# H0BR4.net
KiCad netlist of a schematic drawn in EAGLE
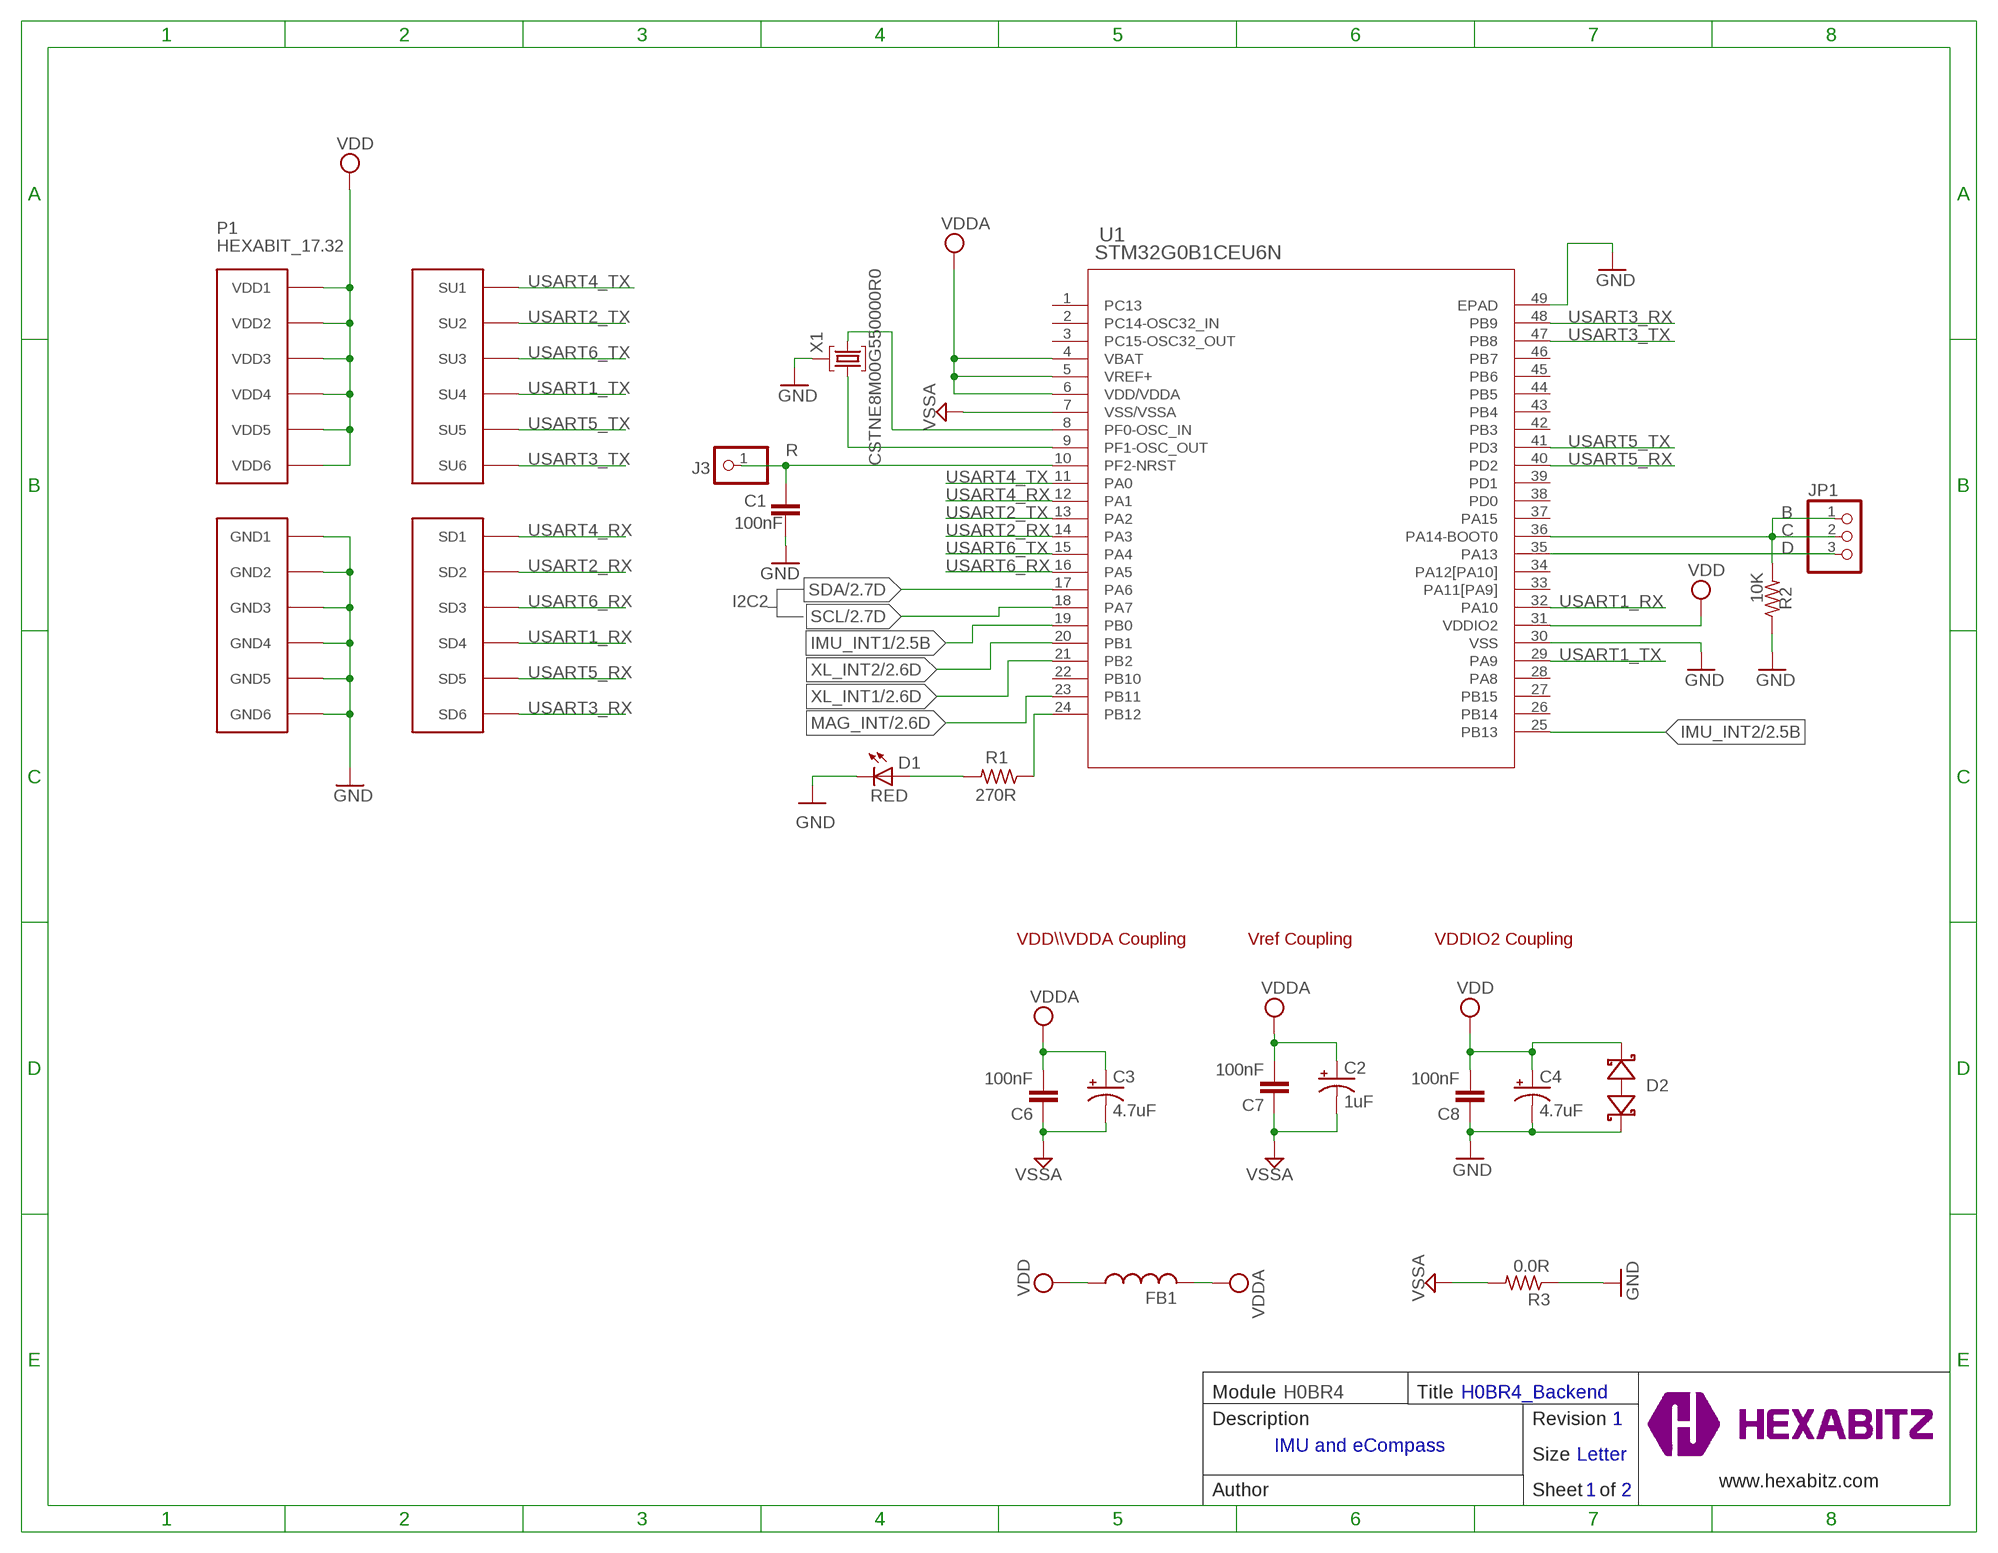
[diagram p0: schematic, sheet 1]
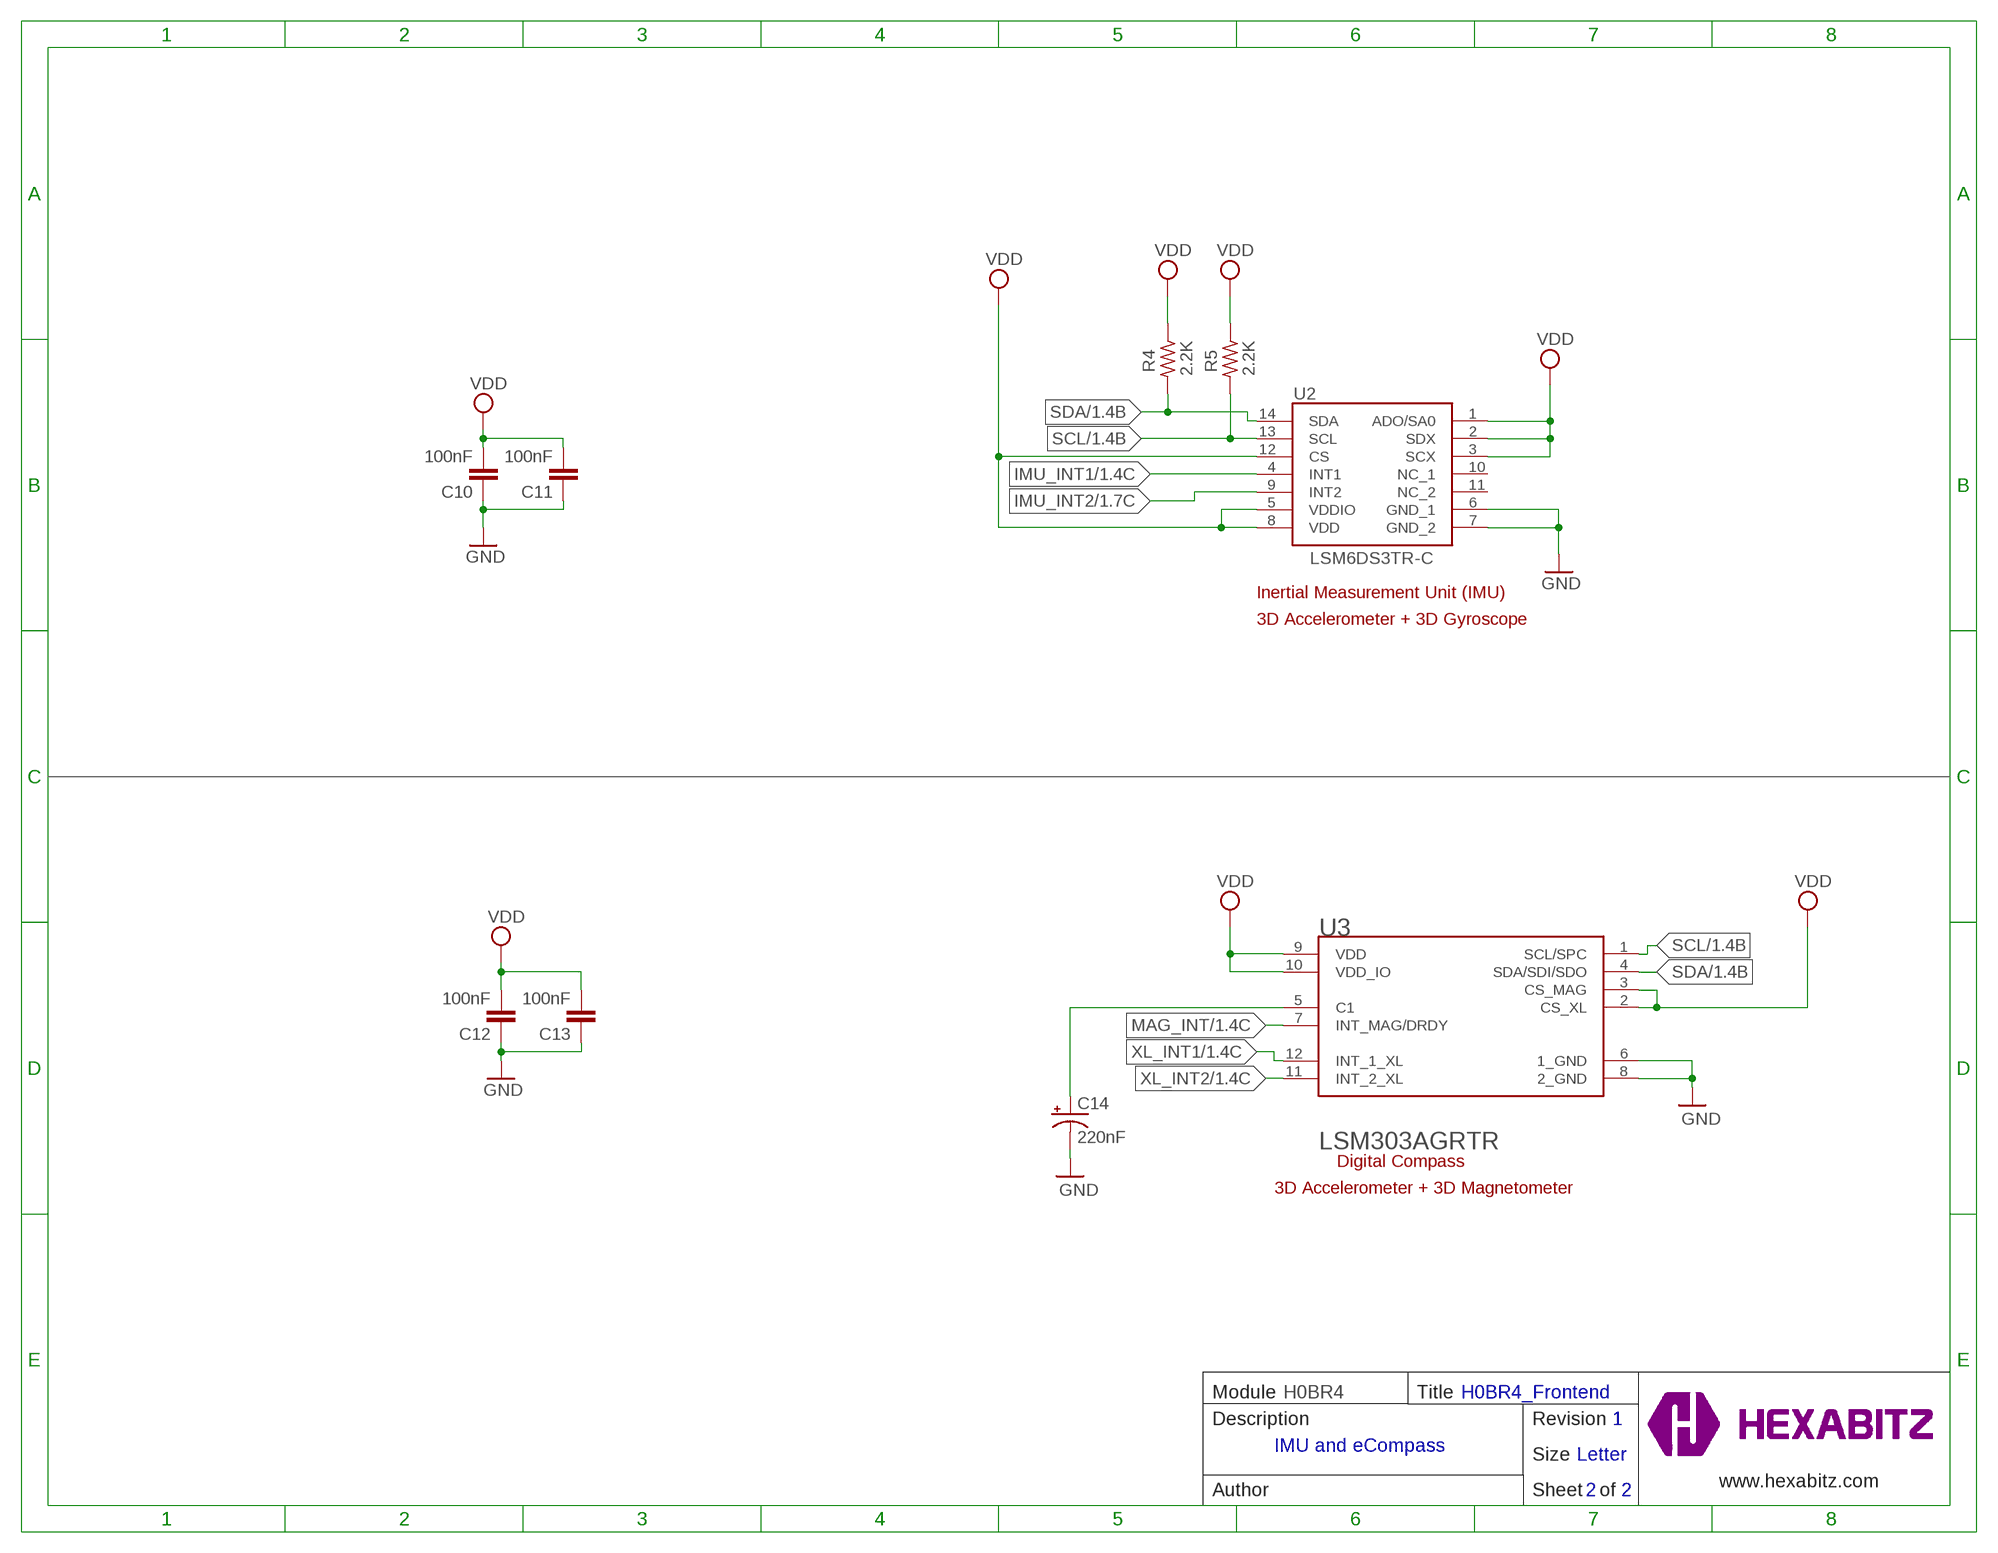
[diagram p1: schematic, sheet 2]

(export (version "E")
  (design (tool "Eeschema 10.0.6"))
  (components
    (comp (ref "C1")
      (value "100nF")
      (footprint "eagle-import:C-0603")
      (fields
        (field (name "CAPACITANCE") "100nF")
        (field (name "MFN") "AVX CORPORATION")
        (field (name "MPN") "'0603YC104K4T2A")
        (field (name "OCTOPART_URL") "'https://octopart.com/0603yc104k4t2a-avx+interconnect+%2F+elco-8120651")
        (field (name "TOLERANCE") "10%")
        (field (name "VOLTAGE_RATING") "16.0 V")
      )
      (libsource (lib "eagle-import") (part "C-0603"))
    )
    (comp (ref "C2")
      (value "1uF")
      (footprint "eagle-import:C-0805-POL")
      (fields
        (field (name "CAPACITANCE") "1.00uF")
        (field (name "MFN") "'YAGEO [VA]")
        (field (name "MPN") "'CC0805KKX7R7BB105")
        (field (name "OCTOPART_URL") "https://octopart.com/cc0805kkx7r7bb105-yageo-8376555?r=sp")
        (field (name "TOLERANCE") "10%")
        (field (name "VOLTAGE_RATING") "16.0 V")
      )
      (libsource (lib "eagle-import") (part "C-0805-POL"))
    )
    (comp (ref "C3")
      (value "4.7uF")
      (footprint "eagle-import:C-0805-POL")
      (fields
        (field (name "CAPACITANCE") "4.7uF")
        (field (name "MFN") "Panasonic")
        (field (name "MPN") "10TPU4R7MSI")
        (field (name "OCTOPART_URL") "https://octopart.com/10tpu4r7msi-panasonic-29487748")
        (field (name "TOLERANCE") "20%")
        (field (name "VOLTAGE_RATING") "10.0 V")
      )
      (libsource (lib "eagle-import") (part "C-0805-POL"))
    )
    (comp (ref "C4")
      (value "4.7uF")
      (footprint "eagle-import:C-0805-POL")
      (fields
        (field (name "CAPACITANCE") "4.7uF")
        (field (name "MFN") "Panasonic")
        (field (name "MPN") "10TPU4R7MSI")
        (field (name "OCTOPART_URL") "https://octopart.com/10tpu4r7msi-panasonic-29487748")
        (field (name "TOLERANCE") "20%")
        (field (name "VOLTAGE_RATING") "10.0 V")
      )
      (libsource (lib "eagle-import") (part "C-0805-POL"))
    )
    (comp (ref "C6")
      (value "100nF")
      (footprint "eagle-import:C-0603")
      (fields
        (field (name "CAPACITANCE") "100nF")
        (field (name "MFN") "AVX CORPORATION")
        (field (name "MPN") "'0603YC104K4T2A")
        (field (name "OCTOPART_URL") "'https://octopart.com/0603yc104k4t2a-avx+interconnect+%2F+elco-8120651")
        (field (name "TOLERANCE") "10%")
        (field (name "VOLTAGE_RATING") "16.0 V")
      )
      (libsource (lib "eagle-import") (part "C-0603"))
    )
    (comp (ref "C7")
      (value "100nF")
      (footprint "eagle-import:C-0603")
      (fields
        (field (name "CAPACITANCE") "100nF")
        (field (name "MFN") "AVX CORPORATION")
        (field (name "MPN") "'0603YC104K4T2A")
        (field (name "OCTOPART_URL") "'https://octopart.com/0603yc104k4t2a-avx+interconnect+%2F+elco-8120651")
        (field (name "TOLERANCE") "10%")
        (field (name "VOLTAGE_RATING") "16.0 V")
      )
      (libsource (lib "eagle-import") (part "C-0603"))
    )
    (comp (ref "C8")
      (value "100nF")
      (footprint "eagle-import:C-0603")
      (fields
        (field (name "CAPACITANCE") "100nF")
        (field (name "MFN") "AVX CORPORATION")
        (field (name "MPN") "'0603YC104K4T2A")
        (field (name "OCTOPART_URL") "'https://octopart.com/0603yc104k4t2a-avx+interconnect+%2F+elco-8120651")
        (field (name "TOLERANCE") "10%")
        (field (name "VOLTAGE_RATING") "16.0 V")
      )
      (libsource (lib "eagle-import") (part "C-0603"))
    )
    (comp (ref "D1")
      (value "RED")
      (footprint "eagle-import:VLMS1300-GS08")
      (fields (field (name "MPN") "VLMS1300-GS08"))
      (libsource (lib "eagle-import") (part "VLMS1300-GS08"))
    )
    (comp (ref "D2")
      (value "BOURNS_CDSOD323-T03SCBOURNS_CDSOD323-T03SC_0_0")
      (footprint "eagle-import:BOURNS_CDSOD323-T03SC_0")
      (fields (field (name "MPN") "CDSOD323-T03SC"))
      (libsource (lib "eagle-import") (part "BOURNS_CDSOD323-T03SCBOURNS_CDSOD323-T03SC_0_0"))
    )
    (comp (ref "FB1")
      (value "FB-TDK_MMZ1608Y300B")
      (footprint "eagle-import:FB-TDK_MMZ1608Y300B")
      (fields
        (field (name "MFN") "TDK ")
        (field (name "MPN") "MMZ1608Y300BTA00")
        (field (name "OCTOPART_URL") "https://octopart.com/mmz1608y300bta00-tdk-7906990?r=sp")
      )
      (libsource (lib "eagle-import") (part "FB-TDK_MMZ1608Y300B"))
    )
    (comp (ref "J3")
      (value "PINHD-1X1")
      (footprint "eagle-import:1X01")
      (fields (field (name "MPN") "87227-1"))
      (libsource (lib "eagle-import") (part "PINHD-1X1"))
    )
    (comp (ref "JP1")
      (value "PINHD-1X3")
      (footprint "eagle-import:1X03")
      (libsource (lib "eagle-import") (part "PINHD-1X3"))
    )
    (comp (ref "P1")
      (value "HEXABIT_17.32")
      (footprint "eagle-import:HEXABIT_17.32")
      (libsource (lib "eagle-import") (part "HEXABIT_?17.32"))
    )
    (comp (ref "R1")
      (value "270R")
      (footprint "eagle-import:R-0603")
      (fields
        (field (name "MFN") "'Panasonic")
        (field (name "MPN") "'ERJ-3GEYJ271V")
        (field (name "OCTOPART_URL") "https://octopart.com/erj-3geyj271v-panasonic-55560546?r=sp")
        (field (name "RESISTANCE") "270R")
      )
      (libsource (lib "eagle-import") (part "R-0603"))
    )
    (comp (ref "R2")
      (value "10K")
      (footprint "eagle-import:R-0603")
      (fields
        (field (name "MFN") "Vishay")
        (field (name "MPN") "'060300J0103T5E")
        (field (name "OCTOPART_URL") "https://octopart.com/search?q=060300J0103T5E&currency=USD&specs=0")
        (field (name "RESISTANCE") "10K")
      )
      (libsource (lib "eagle-import") (part "R-0603"))
    )
    (comp (ref "R3")
      (value "0.0R")
      (footprint "eagle-import:R-0603")
      (fields
        (field (name "MFN") "YAGEO [VR]")
        (field (name "MPN") "RC0603JR-070RL")
        (field (name "OCTOPART_URL") "https://octopart.com/rc0603jr-070rl-yageo-1241539?r=sp")
        (field (name "RESISTANCE") "0R")
      )
      (libsource (lib "eagle-import") (part "R-0603"))
    )
    (comp (ref "TRIMBLE-LOGO1")
      (value "HEXA-LOGO")
      (footprint "eagle-import:HEXA-LOGO")
      (libsource (lib "eagle-import") (part "HEXA-LOGO"))
    )
    (comp (ref "U1")
      (value "STM32G0B1CEU6N")
      (footprint "eagle-import:HEXABITZ_ICS_QFN_B1CEU6_STM-L")
      (libsource (lib "eagle-import") (part "STM32G0B1CEU6N"))
    )
    (comp (ref "X1")
      (value "CSTNE8M00G550000R0")
      (footprint "eagle-import:XTALL_CSTCE8M00G52")
      (fields
        (field (name "MPN") "CSTCE8M00G52Z-R0")
        (field (name "MPN_1") "CSTNE8M00G550000R0")
        (field (name "OCTOPART_URL") "https://octopart.com/cstne8m00g550000r0-murata-91406934?r=sp")
      )
      (libsource (lib "eagle-import") (part "XTALL_CSTCE8M00G52"))
    )
    (comp (ref "C10")
      (value "100nF")
      (footprint "eagle-import:C-0603")
      (fields
        (field (name "CAPACITANCE") "100nF")
        (field (name "MFN") "AVX CORPORATION")
        (field (name "MPN") "'0603YC104K4T2A")
        (field (name "OCTOPART_URL") "'https://octopart.com/0603yc104k4t2a-avx+interconnect+%2F+elco-8120651")
        (field (name "TOLERANCE") "10%")
        (field (name "VOLTAGE_RATING") "16.0 V")
      )
      (libsource (lib "eagle-import") (part "C-0603"))
    )
    (comp (ref "C11")
      (value "100nF")
      (footprint "eagle-import:C-0603")
      (fields
        (field (name "CAPACITANCE") "100nF")
        (field (name "MFN") "AVX CORPORATION")
        (field (name "MPN") "'0603YC104K4T2A")
        (field (name "OCTOPART_URL") "'https://octopart.com/0603yc104k4t2a-avx+interconnect+%2F+elco-8120651")
        (field (name "TOLERANCE") "10%")
        (field (name "VOLTAGE_RATING") "16.0 V")
      )
      (libsource (lib "eagle-import") (part "C-0603"))
    )
    (comp (ref "C12")
      (value "100nF")
      (footprint "eagle-import:C-0603")
      (fields
        (field (name "CAPACITANCE") "100nF")
        (field (name "MFN") "AVX CORPORATION")
        (field (name "MPN") "'0603YC104K4T2A")
        (field (name "OCTOPART_URL") "'https://octopart.com/0603yc104k4t2a-avx+interconnect+%2F+elco-8120651")
        (field (name "TOLERANCE") "10%")
        (field (name "VOLTAGE_RATING") "16.0 V")
      )
      (libsource (lib "eagle-import") (part "C-0603"))
    )
    (comp (ref "C13")
      (value "100nF")
      (footprint "eagle-import:C-0603")
      (fields
        (field (name "CAPACITANCE") "100nF")
        (field (name "MFN") "AVX CORPORATION")
        (field (name "MPN") "'0603YC104K4T2A")
        (field (name "OCTOPART_URL") "'https://octopart.com/0603yc104k4t2a-avx+interconnect+%2F+elco-8120651")
        (field (name "TOLERANCE") "10%")
        (field (name "VOLTAGE_RATING") "16.0 V")
      )
      (libsource (lib "eagle-import") (part "C-0603"))
    )
    (comp (ref "C14")
      (value "220nF")
      (footprint "eagle-import:C-0805-POL")
      (fields
        (field (name "CAPACITANCE") "4.7uF")
        (field (name "MFN") "KEMET ")
        (field (name "MPN") "C0805C224K1RACTU")
        (field (name "OCTOPART_URL") "https://octopart.com/c0805c224k1ractu-kemet-12818106?r=sp")
        (field (name "TOLERANCE") "20%")
        (field (name "VOLTAGE_RATING") "10.0 V")
      )
      (libsource (lib "eagle-import") (part "C-0805-POL"))
    )
    (comp (ref "R4")
      (value "2.2K")
      (footprint "eagle-import:R-0603")
      (fields
        (field (name "MFN") "Yageo")
        (field (name "MPN") "RC0603FR-072K2L")
        (field (name "OCTOPART_URL") "https://octopart.com/rc0603fr-072k2l-yageo-1214512?r=sp")
        (field (name "RESISTANCE") "2.2K Ohm")
        (field (name "TOLERANCE") "5%")
      )
      (libsource (lib "eagle-import") (part "R-0603"))
    )
    (comp (ref "R5")
      (value "2.2K")
      (footprint "eagle-import:R-0603")
      (fields
        (field (name "MFN") "Yageo")
        (field (name "MPN") "RC0603FR-072K2L")
        (field (name "OCTOPART_URL") "https://octopart.com/rc0603fr-072k2l-yageo-1214512?r=sp")
        (field (name "RESISTANCE") "2.2K Ohm")
        (field (name "TOLERANCE") "5%")
      )
      (libsource (lib "eagle-import") (part "R-0603"))
    )
    (comp (ref "U2")
      (value "LSM6DS3TR-C")
      (footprint "eagle-import:LGA-14(2.5X3X0.86)")
      (libsource (lib "eagle-import") (part "LSM6DS3TR-C"))
    )
    (comp (ref "U3")
      (value "STMICROELECTRONICS_LSM303AGRTRSTMICROELECTRONICS_LSM303AGRTR_0_0")
      (footprint "eagle-import:STMICROELECTRONICS_LSM303AGRTR_0")
      (fields
        (field (name "DIGIKEY_PART_NUMBER") "497-16527-1-ND")
        (field (name "MOUSER_PART_NUMBER") "511-LSM303AGRTR")
        (field (name "MPN") "LSM303AGRTR")
      )
      (libsource (lib "eagle-import") (part "STMICROELECTRONICS_LSM303AGRTRSTMICROELECTRONICS_LSM303AGRTR_0_0"))
    )
  )
  (nets
    (net (code "1") (name "C") (class "Default")
      (node (ref "JP1") (pin "1") (pinfunction "1_1") (pintype "passive"))
      (node (ref "JP1") (pin "2") (pinfunction "2_2") (pintype "passive"))
      (node (ref "R2") (pin "2") (pinfunction "2_2") (pintype "passive"))
      (node (ref "U1") (pin "36") (pinfunction "PA14-BOOT0_36") (pintype "bidirectional"))
    )
    (net (code "2") (name "D") (class "Default")
      (node (ref "JP1") (pin "3") (pinfunction "3_3") (pintype "passive"))
      (node (ref "U1") (pin "35") (pinfunction "PA13_35") (pintype "bidirectional"))
    )
    (net (code "3") (name "GND") (class "Default")
      (node (ref "C1") (pin "1") (pinfunction "1_1") (pintype "passive"))
      (node (ref "C10") (pin "1") (pinfunction "1_1") (pintype "passive"))
      (node (ref "C11") (pin "1") (pinfunction "1_1") (pintype "passive"))
      (node (ref "C12") (pin "1") (pinfunction "1_1") (pintype "passive"))
      (node (ref "C13") (pin "1") (pinfunction "1_1") (pintype "passive"))
      (node (ref "C14") (pin "2") (pinfunction "-_2") (pintype "passive"))
      (node (ref "C4") (pin "2") (pinfunction "-_2") (pintype "passive"))
      (node (ref "C8") (pin "1") (pinfunction "1_1") (pintype "passive"))
      (node (ref "D1") (pin "C") (pinfunction "C_C") (pintype "passive"))
      (node (ref "D2") (pin "1") (pinfunction "A_1") (pintype "passive"))
      (node (ref "P1") (pin "PAD_PD10") (pinfunction "GND4_PAD_PD10") (pintype "power_in"))
      (node (ref "P1") (pin "PAD_PD11") (pinfunction "GND5_PAD_PD11") (pintype "power_in"))
      (node (ref "P1") (pin "PAD_PD12") (pinfunction "GND6_PAD_PD12") (pintype "power_in"))
      (node (ref "P1") (pin "PAD_PD7") (pinfunction "GND1_PAD_PD7") (pintype "power_in"))
      (node (ref "P1") (pin "PAD_PD8") (pinfunction "GND2_PAD_PD8") (pintype "power_in"))
      (node (ref "P1") (pin "PAD_PD9") (pinfunction "GND3_PAD_PD9") (pintype "power_in"))
      (node (ref "R2") (pin "1") (pinfunction "1_1") (pintype "passive"))
      (node (ref "R3") (pin "1") (pinfunction "1_1") (pintype "passive"))
      (node (ref "U1") (pin "30") (pinfunction "VSS_30") (pintype "passive"))
      (node (ref "U1") (pin "49") (pinfunction "EPAD_49") (pintype "passive"))
      (node (ref "U2") (pin "6") (pinfunction "GND_1_6") (pintype "bidirectional"))
      (node (ref "U2") (pin "7") (pinfunction "GND_2_7") (pintype "bidirectional"))
      (node (ref "U3") (pin "6") (pinfunction "1_GND_6") (pintype "power_in"))
      (node (ref "U3") (pin "8") (pinfunction "2_GND_8") (pintype "power_in"))
      (node (ref "X1") (pin "P$2") (pinfunction "2_P$2") (pintype "passive"))
    )
    (net (code "4") (name "GND1") (class "Default")
      (node (ref "C2") (pin "2") (pinfunction "-_2") (pintype "passive"))
      (node (ref "C3") (pin "2") (pinfunction "-_2") (pintype "passive"))
      (node (ref "C6") (pin "1") (pinfunction "1_1") (pintype "passive"))
      (node (ref "C7") (pin "1") (pinfunction "1_1") (pintype "passive"))
      (node (ref "R3") (pin "2") (pinfunction "2_2") (pintype "passive"))
      (node (ref "U1") (pin "7") (pinfunction "VSS/VSSA_7") (pintype "passive"))
    )
    (net (code "5") (name "IMU_INT1") (class "Default")
      (node (ref "U1") (pin "19") (pinfunction "PB0_19") (pintype "bidirectional"))
      (node (ref "U2") (pin "4") (pinfunction "INT1_4") (pintype "bidirectional"))
    )
    (net (code "6") (name "IMU_INT2") (class "Default")
      (node (ref "U1") (pin "25") (pinfunction "PB13_25") (pintype "bidirectional"))
      (node (ref "U2") (pin "9") (pinfunction "INT2_9") (pintype "bidirectional"))
    )
    (net (code "7") (name "MAG_INT") (class "Default")
      (node (ref "U1") (pin "23") (pinfunction "PB11_23") (pintype "bidirectional"))
      (node (ref "U3") (pin "7") (pinfunction "INT_MAG/DRDY_7") (pintype "input"))
    )
    (net (code "8") (name "Net-(C14-+)") (class "Default")
      (node (ref "C14") (pin "1") (pinfunction "+_1") (pintype "passive"))
      (node (ref "U3") (pin "5") (pinfunction "C1_5") (pintype "passive"))
    )
    (net (code "9") (name "Net-(D1-PadA)") (class "Default")
      (node (ref "D1") (pin "A") (pinfunction "A_A") (pintype "passive"))
      (node (ref "R1") (pin "2") (pinfunction "2_2") (pintype "passive"))
    )
    (net (code "10") (name "Net-(U1-PB12)") (class "Default")
      (node (ref "R1") (pin "1") (pinfunction "1_1") (pintype "passive"))
      (node (ref "U1") (pin "24") (pinfunction "PB12_24") (pintype "bidirectional"))
    )
    (net (code "11") (name "Net-(U1-PF0-OSC_IN)") (class "Default")
      (node (ref "U1") (pin "8") (pinfunction "PF0-OSC_IN_8") (pintype "bidirectional"))
      (node (ref "X1") (pin "P$1") (pinfunction "1_P$1") (pintype "passive"))
    )
    (net (code "12") (name "Net-(U1-PF1-OSC_OUT)") (class "Default")
      (node (ref "U1") (pin "9") (pinfunction "PF1-OSC_OUT_9") (pintype "bidirectional"))
      (node (ref "X1") (pin "P$3") (pinfunction "3_P$3") (pintype "passive"))
    )
    (net (code "13") (name "R") (class "Default")
      (node (ref "C1") (pin "2") (pinfunction "2_2") (pintype "passive"))
      (node (ref "J3") (pin "1") (pinfunction "1_1") (pintype "passive"))
      (node (ref "U1") (pin "10") (pinfunction "PF2-NRST_10") (pintype "bidirectional"))
    )
    (net (code "14") (name "SCL") (class "Default")
      (node (ref "R5") (pin "2") (pinfunction "2_2") (pintype "passive"))
      (node (ref "U1") (pin "18") (pinfunction "PA7_18") (pintype "bidirectional"))
      (node (ref "U2") (pin "13") (pinfunction "SCL_13") (pintype "bidirectional"))
      (node (ref "U3") (pin "1") (pinfunction "SCL/SPC_1") (pintype "input"))
    )
    (net (code "15") (name "SDA") (class "Default")
      (node (ref "R4") (pin "2") (pinfunction "2_2") (pintype "passive"))
      (node (ref "U1") (pin "17") (pinfunction "PA6_17") (pintype "bidirectional"))
      (node (ref "U2") (pin "14") (pinfunction "SDA_14") (pintype "bidirectional"))
      (node (ref "U3") (pin "4") (pinfunction "SDA/SDI/SDO_4") (pintype "bidirectional"))
    )
    (net (code "16") (name "USART1_RX") (class "Default")
      (node (ref "P1") (pin "PAD_PD4") (pinfunction "SD4_PAD_PD4") (pintype "bidirectional"))
      (node (ref "U1") (pin "32") (pinfunction "PA10_32") (pintype "bidirectional"))
    )
    (net (code "17") (name "USART1_TX") (class "Default")
      (node (ref "P1") (pin "PAD_PU4") (pinfunction "SU4_PAD_PU4") (pintype "bidirectional"))
      (node (ref "U1") (pin "29") (pinfunction "PA9_29") (pintype "bidirectional"))
    )
    (net (code "18") (name "USART2_RX") (class "Default")
      (node (ref "P1") (pin "PAD_PD2") (pinfunction "SD2_PAD_PD2") (pintype "bidirectional"))
      (node (ref "U1") (pin "14") (pinfunction "PA3_14") (pintype "bidirectional"))
    )
    (net (code "19") (name "USART2_TX") (class "Default")
      (node (ref "P1") (pin "PAD_PU2") (pinfunction "SU2_PAD_PU2") (pintype "bidirectional"))
      (node (ref "U1") (pin "13") (pinfunction "PA2_13") (pintype "bidirectional"))
    )
    (net (code "20") (name "USART3_RX") (class "Default")
      (node (ref "P1") (pin "PAD_PD6") (pinfunction "SD6_PAD_PD6") (pintype "bidirectional"))
      (node (ref "U1") (pin "48") (pinfunction "PB9_48") (pintype "bidirectional"))
    )
    (net (code "21") (name "USART3_TX") (class "Default")
      (node (ref "P1") (pin "PAD_PU6") (pinfunction "SU6_PAD_PU6") (pintype "bidirectional"))
      (node (ref "U1") (pin "47") (pinfunction "PB8_47") (pintype "bidirectional"))
    )
    (net (code "22") (name "USART4_RX") (class "Default")
      (node (ref "P1") (pin "PAD_PD1") (pinfunction "SD1_PAD_PD1") (pintype "bidirectional"))
      (node (ref "U1") (pin "12") (pinfunction "PA1_12") (pintype "bidirectional"))
    )
    (net (code "23") (name "USART4_TX") (class "Default")
      (node (ref "P1") (pin "PAD_PU1") (pinfunction "SU1_PAD_PU1") (pintype "bidirectional"))
      (node (ref "U1") (pin "11") (pinfunction "PA0_11") (pintype "bidirectional"))
    )
    (net (code "24") (name "USART5_RX") (class "Default")
      (node (ref "P1") (pin "PAD_PD5") (pinfunction "SD5_PAD_PD5") (pintype "bidirectional"))
      (node (ref "U1") (pin "40") (pinfunction "PD2_40") (pintype "bidirectional"))
    )
    (net (code "25") (name "USART5_TX") (class "Default")
      (node (ref "P1") (pin "PAD_PU5") (pinfunction "SU5_PAD_PU5") (pintype "bidirectional"))
      (node (ref "U1") (pin "41") (pinfunction "PD3_41") (pintype "bidirectional"))
    )
    (net (code "26") (name "USART6_RX") (class "Default")
      (node (ref "P1") (pin "PAD_PD3") (pinfunction "SD3_PAD_PD3") (pintype "bidirectional"))
      (node (ref "U1") (pin "16") (pinfunction "PA5_16") (pintype "bidirectional"))
    )
    (net (code "27") (name "USART6_TX") (class "Default")
      (node (ref "P1") (pin "PAD_PU3") (pinfunction "SU3_PAD_PU3") (pintype "bidirectional"))
      (node (ref "U1") (pin "15") (pinfunction "PA4_15") (pintype "bidirectional"))
    )
    (net (code "28") (name "VCC") (class "Default")
      (node (ref "C2") (pin "1") (pinfunction "+_1") (pintype "passive"))
      (node (ref "C3") (pin "1") (pinfunction "+_1") (pintype "passive"))
      (node (ref "C6") (pin "2") (pinfunction "2_2") (pintype "passive"))
      (node (ref "C7") (pin "2") (pinfunction "2_2") (pintype "passive"))
      (node (ref "FB1") (pin "2") (pinfunction "2_2") (pintype "passive"))
      (node (ref "U1") (pin "4") (pinfunction "VBAT_4") (pintype "power_in"))
      (node (ref "U1") (pin "5") (pinfunction "VREF+_5") (pintype "power_in"))
      (node (ref "U1") (pin "6") (pinfunction "VDD/VDDA_6") (pintype "power_in"))
    )
    (net (code "29") (name "VDD") (class "Default")
      (node (ref "C10") (pin "2") (pinfunction "2_2") (pintype "passive"))
      (node (ref "C11") (pin "2") (pinfunction "2_2") (pintype "passive"))
      (node (ref "C12") (pin "2") (pinfunction "2_2") (pintype "passive"))
      (node (ref "C13") (pin "2") (pinfunction "2_2") (pintype "passive"))
      (node (ref "C4") (pin "1") (pinfunction "+_1") (pintype "passive"))
      (node (ref "C8") (pin "2") (pinfunction "2_2") (pintype "passive"))
      (node (ref "D2") (pin "2") (pinfunction "C_2") (pintype "passive"))
      (node (ref "FB1") (pin "1") (pinfunction "1_1") (pintype "passive"))
      (node (ref "P1") (pin "PAD_PU10") (pinfunction "VDD4_PAD_PU10") (pintype "power_in"))
      (node (ref "P1") (pin "PAD_PU11") (pinfunction "VDD5_PAD_PU11") (pintype "power_in"))
      (node (ref "P1") (pin "PAD_PU12") (pinfunction "VDD6_PAD_PU12") (pintype "power_in"))
      (node (ref "P1") (pin "PAD_PU7") (pinfunction "VDD1_PAD_PU7") (pintype "power_in"))
      (node (ref "P1") (pin "PAD_PU8") (pinfunction "VDD2_PAD_PU8") (pintype "power_in"))
      (node (ref "P1") (pin "PAD_PU9") (pinfunction "VDD3_PAD_PU9") (pintype "power_in"))
      (node (ref "R4") (pin "1") (pinfunction "1_1") (pintype "passive"))
      (node (ref "R5") (pin "1") (pinfunction "1_1") (pintype "passive"))
      (node (ref "U1") (pin "31") (pinfunction "VDDIO2_31") (pintype "power_in"))
      (node (ref "U2") (pin "1") (pinfunction "ADO/SA0_1") (pintype "bidirectional"))
      (node (ref "U2") (pin "12") (pinfunction "CS_12") (pintype "bidirectional"))
      (node (ref "U2") (pin "2") (pinfunction "SDX_2") (pintype "bidirectional"))
      (node (ref "U2") (pin "3") (pinfunction "SCX_3") (pintype "bidirectional"))
      (node (ref "U2") (pin "5") (pinfunction "VDDIO_5") (pintype "bidirectional"))
      (node (ref "U2") (pin "8") (pinfunction "VDD_8") (pintype "bidirectional"))
      (node (ref "U3") (pin "10") (pinfunction "VDD_IO_10") (pintype "power_in"))
      (node (ref "U3") (pin "2") (pinfunction "CS_XL_2") (pintype "input"))
      (node (ref "U3") (pin "3") (pinfunction "CS_MAG_3") (pintype "input"))
      (node (ref "U3") (pin "9") (pinfunction "VDD_9") (pintype "power_in"))
    )
    (net (code "30") (name "XL_INT1") (class "Default")
      (node (ref "U1") (pin "21") (pinfunction "PB2_21") (pintype "bidirectional"))
      (node (ref "U3") (pin "12") (pinfunction "INT_1_XL_12") (pintype "input"))
    )
    (net (code "31") (name "XL_INT2") (class "Default")
      (node (ref "U1") (pin "20") (pinfunction "PB1_20") (pintype "bidirectional"))
      (node (ref "U3") (pin "11") (pinfunction "INT_2_XL_11") (pintype "input"))
    )
    (net (code "32") (name "unconnected-(U1-PA8-Pad28)") (class "Default")
      (node (ref "U1") (pin "28") (pinfunction "PA8_28") (pintype "bidirectional"))
    )
    (net (code "33") (name "unconnected-(U1-PA11[PA9]-Pad33)") (class "Default")
      (node (ref "U1") (pin "33") (pinfunction "PA11[PA9]_33") (pintype "bidirectional"))
    )
    (net (code "34") (name "unconnected-(U1-PA12[PA10]-Pad34)") (class "Default")
      (node (ref "U1") (pin "34") (pinfunction "PA12[PA10]_34") (pintype "bidirectional"))
    )
    (net (code "35") (name "unconnected-(U1-PA15-Pad37)") (class "Default")
      (node (ref "U1") (pin "37") (pinfunction "PA15_37") (pintype "bidirectional"))
    )
    (net (code "36") (name "unconnected-(U1-PB3-Pad42)") (class "Default")
      (node (ref "U1") (pin "42") (pinfunction "PB3_42") (pintype "bidirectional"))
    )
    (net (code "37") (name "unconnected-(U1-PB4-Pad43)") (class "Default")
      (node (ref "U1") (pin "43") (pinfunction "PB4_43") (pintype "bidirectional"))
    )
    (net (code "38") (name "unconnected-(U1-PB5-Pad44)") (class "Default")
      (node (ref "U1") (pin "44") (pinfunction "PB5_44") (pintype "bidirectional"))
    )
    (net (code "39") (name "unconnected-(U1-PB6-Pad45)") (class "Default")
      (node (ref "U1") (pin "45") (pinfunction "PB6_45") (pintype "bidirectional"))
    )
    (net (code "40") (name "unconnected-(U1-PB7-Pad46)") (class "Default")
      (node (ref "U1") (pin "46") (pinfunction "PB7_46") (pintype "bidirectional"))
    )
    (net (code "41") (name "unconnected-(U1-PB10-Pad22)") (class "Default")
      (node (ref "U1") (pin "22") (pinfunction "PB10_22") (pintype "bidirectional"))
    )
    (net (code "42") (name "unconnected-(U1-PB14-Pad26)") (class "Default")
      (node (ref "U1") (pin "26") (pinfunction "PB14_26") (pintype "bidirectional"))
    )
    (net (code "43") (name "unconnected-(U1-PB15-Pad27)") (class "Default")
      (node (ref "U1") (pin "27") (pinfunction "PB15_27") (pintype "bidirectional"))
    )
    (net (code "44") (name "unconnected-(U1-PC13-Pad1)") (class "Default")
      (node (ref "U1") (pin "1") (pinfunction "PC13_1") (pintype "bidirectional"))
    )
    (net (code "45") (name "unconnected-(U1-PC14-OSC32_IN-Pad2)") (class "Default")
      (node (ref "U1") (pin "2") (pinfunction "PC14-OSC32_IN_2") (pintype "bidirectional"))
    )
    (net (code "46") (name "unconnected-(U1-PC15-OSC32_OUT-Pad3)") (class "Default")
      (node (ref "U1") (pin "3") (pinfunction "PC15-OSC32_OUT_3") (pintype "bidirectional"))
    )
    (net (code "47") (name "unconnected-(U1-PD0-Pad38)") (class "Default")
      (node (ref "U1") (pin "38") (pinfunction "PD0_38") (pintype "bidirectional"))
    )
    (net (code "48") (name "unconnected-(U1-PD1-Pad39)") (class "Default")
      (node (ref "U1") (pin "39") (pinfunction "PD1_39") (pintype "bidirectional"))
    )
    (net (code "49") (name "unconnected-(U2-NC_1-Pad10)") (class "Default")
      (node (ref "U2") (pin "10") (pinfunction "NC_1_10") (pintype "bidirectional"))
    )
    (net (code "50") (name "unconnected-(U2-NC_2-Pad11)") (class "Default")
      (node (ref "U2") (pin "11") (pinfunction "NC_2_11") (pintype "bidirectional"))
    )
  )
)
